# max21100_v3.net
KiCad netlist of a schematic drawn in EAGLE
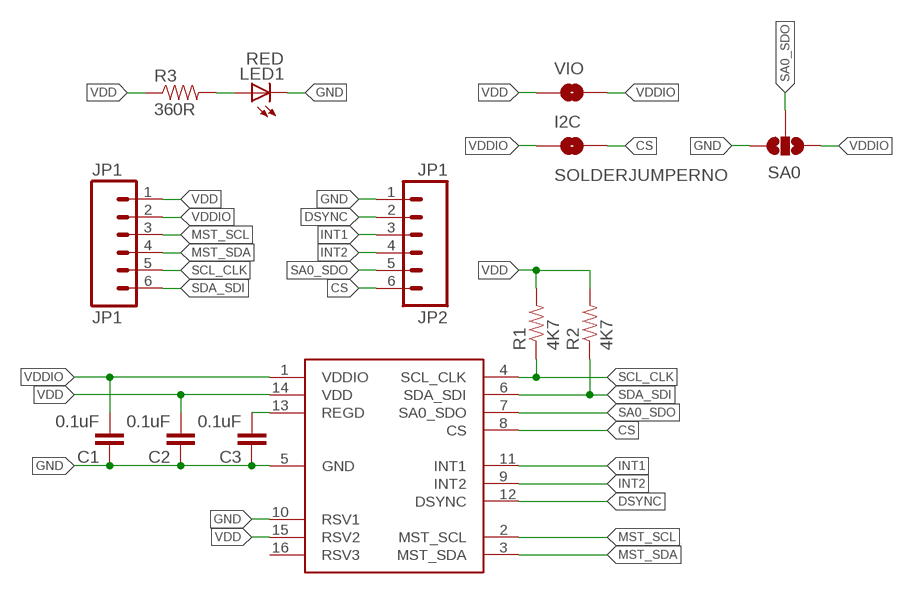
[diagram p0: schematic, sheet 1]

(export (version "E")
  (design (tool "Eeschema 10.0.6"))
  (components
    (comp (ref "C1")
      (value "0.1uF")
      (footprint "eagle-import:0603-CAP")
      (libsource (lib "eagle-import") (part "CAP0603-CAP"))
    )
    (comp (ref "C2")
      (value "0.1uF")
      (footprint "eagle-import:0603-CAP")
      (libsource (lib "eagle-import") (part "CAP0603-CAP"))
    )
    (comp (ref "C3")
      (value "0.1uF")
      (footprint "eagle-import:0603-CAP")
      (libsource (lib "eagle-import") (part "CAP0603-CAP"))
    )
    (comp (ref "I2C")
      (value "SOLDERJUMPERNO")
      (footprint "eagle-import:SJ_2S-NO")
      (libsource (lib "eagle-import") (part "SOLDERJUMPERNO"))
    )
    (comp (ref "JP1")
      (value "JP1")
      (footprint "eagle-import:1X06")
      (libsource (lib "eagle-import") (part "M06SIP"))
    )
    (comp (ref "JP2")
      (value "JP1")
      (footprint "eagle-import:1X06")
      (libsource (lib "eagle-import") (part "M06SIP"))
    )
    (comp (ref "LED1")
      (value "RED")
      (footprint "eagle-import:CHIP-LED0603")
      (libsource (lib "eagle-import") (part "LEDCHIP-LED0603"))
    )
    (comp (ref "R1")
      (value "4K7")
      (footprint "eagle-import:0603-RES")
      (libsource (lib "eagle-import") (part "RESISTOR0603-RES"))
    )
    (comp (ref "R2")
      (value "4K7")
      (footprint "eagle-import:0603-RES")
      (libsource (lib "eagle-import") (part "RESISTOR0603-RES"))
    )
    (comp (ref "R3")
      (value "360R")
      (footprint "eagle-import:0603-RES")
      (libsource (lib "eagle-import") (part "RESISTOR0603-RES"))
    )
    (comp (ref "SA0")
      (value "SOLDERJUMPER_2WAYS")
      (footprint "eagle-import:SJ_3")
      (libsource (lib "eagle-import") (part "SOLDERJUMPER_2WAYS"))
    )
    (comp (ref "U$1")
      (value "MAX21100")
      (footprint "eagle-import:MAX21100")
      (libsource (lib "eagle-import") (part "MAX21100"))
    )
    (comp (ref "VIO")
      (value "SOLDERJUMPERTRACE")
      (footprint "eagle-import:SJ_2S-TRACE")
      (libsource (lib "eagle-import") (part "SOLDERJUMPERTRACE"))
    )
  )
  (nets
    (net (code "1") (name "CS") (class "Default")
      (node (ref "I2C") (pin "2") (pinfunction "2_2") (pintype "passive"))
      (node (ref "JP2") (pin "6") (pinfunction "6_6") (pintype "passive"))
      (node (ref "U$1") (pin "8") (pinfunction "CS_8") (pintype "bidirectional"))
    )
    (net (code "2") (name "DSYNC") (class "Default")
      (node (ref "JP2") (pin "2") (pinfunction "2_2") (pintype "passive"))
      (node (ref "U$1") (pin "12") (pinfunction "DSYNC_12") (pintype "bidirectional"))
    )
    (net (code "3") (name "GND") (class "Default")
      (node (ref "C1") (pin "1") (pinfunction "1_1") (pintype "passive"))
      (node (ref "C2") (pin "1") (pinfunction "1_1") (pintype "passive"))
      (node (ref "C3") (pin "1") (pinfunction "1_1") (pintype "passive"))
      (node (ref "JP2") (pin "1") (pinfunction "1_1") (pintype "passive"))
      (node (ref "LED1") (pin "C") (pinfunction "C_C") (pintype "passive"))
      (node (ref "SA0") (pin "1") (pinfunction "1_1") (pintype "passive"))
      (node (ref "U$1") (pin "10") (pinfunction "RSV1_10") (pintype "bidirectional"))
      (node (ref "U$1") (pin "5") (pinfunction "GND_5") (pintype "bidirectional"))
    )
    (net (code "4") (name "INT1") (class "Default")
      (node (ref "JP2") (pin "3") (pinfunction "3_3") (pintype "passive"))
      (node (ref "U$1") (pin "11") (pinfunction "INT1_11") (pintype "bidirectional"))
    )
    (net (code "5") (name "INT2") (class "Default")
      (node (ref "JP2") (pin "4") (pinfunction "4_4") (pintype "passive"))
      (node (ref "U$1") (pin "9") (pinfunction "INT2_9") (pintype "bidirectional"))
    )
    (net (code "6") (name "MST_SCL") (class "Default")
      (node (ref "JP1") (pin "3") (pinfunction "3_3") (pintype "passive"))
      (node (ref "U$1") (pin "2") (pinfunction "MST_SCL_2") (pintype "bidirectional"))
    )
    (net (code "7") (name "MST_SDA") (class "Default")
      (node (ref "JP1") (pin "4") (pinfunction "4_4") (pintype "passive"))
      (node (ref "U$1") (pin "3") (pinfunction "MST_SDA_3") (pintype "bidirectional"))
    )
    (net (code "8") (name "Net-(LED1-PadA)") (class "Default")
      (node (ref "LED1") (pin "A") (pinfunction "A_A") (pintype "passive"))
      (node (ref "R3") (pin "2") (pinfunction "2_2") (pintype "passive"))
    )
    (net (code "9") (name "Net-(U$1-REGD)") (class "Default")
      (node (ref "C3") (pin "2") (pinfunction "2_2") (pintype "passive"))
      (node (ref "U$1") (pin "13") (pinfunction "REGD_13") (pintype "bidirectional"))
    )
    (net (code "10") (name "SA0_SDO") (class "Default")
      (node (ref "JP2") (pin "5") (pinfunction "5_5") (pintype "passive"))
      (node (ref "SA0") (pin "2") (pinfunction "2_2") (pintype "passive"))
      (node (ref "U$1") (pin "7") (pinfunction "SA0_SDO_7") (pintype "bidirectional"))
    )
    (net (code "11") (name "SCL_CLK") (class "Default")
      (node (ref "JP1") (pin "5") (pinfunction "5_5") (pintype "passive"))
      (node (ref "R1") (pin "1") (pinfunction "1_1") (pintype "passive"))
      (node (ref "U$1") (pin "4") (pinfunction "SCL_CLK_4") (pintype "bidirectional"))
    )
    (net (code "12") (name "SDA_SDI") (class "Default")
      (node (ref "JP1") (pin "6") (pinfunction "6_6") (pintype "passive"))
      (node (ref "R2") (pin "1") (pinfunction "1_1") (pintype "passive"))
      (node (ref "U$1") (pin "6") (pinfunction "SDA_SDI_6") (pintype "bidirectional"))
    )
    (net (code "13") (name "VDD") (class "Default")
      (node (ref "C2") (pin "2") (pinfunction "2_2") (pintype "passive"))
      (node (ref "JP1") (pin "1") (pinfunction "1_1") (pintype "passive"))
      (node (ref "R1") (pin "2") (pinfunction "2_2") (pintype "passive"))
      (node (ref "R2") (pin "2") (pinfunction "2_2") (pintype "passive"))
      (node (ref "R3") (pin "1") (pinfunction "1_1") (pintype "passive"))
      (node (ref "U$1") (pin "14") (pinfunction "VDD_14") (pintype "bidirectional"))
      (node (ref "U$1") (pin "15") (pinfunction "RSV2_15") (pintype "bidirectional"))
      (node (ref "VIO") (pin "1") (pinfunction "1_1") (pintype "passive"))
    )
    (net (code "14") (name "VDDIO") (class "Default")
      (node (ref "C1") (pin "2") (pinfunction "2_2") (pintype "passive"))
      (node (ref "I2C") (pin "1") (pinfunction "1_1") (pintype "passive"))
      (node (ref "JP1") (pin "2") (pinfunction "2_2") (pintype "passive"))
      (node (ref "SA0") (pin "3") (pinfunction "3_3") (pintype "passive"))
      (node (ref "U$1") (pin "1") (pinfunction "VDDIO_1") (pintype "bidirectional"))
      (node (ref "VIO") (pin "2") (pinfunction "2_2") (pintype "passive"))
    )
    (net (code "15") (name "unconnected-(U$1-RSV3-Pad16)") (class "Default")
      (node (ref "U$1") (pin "16") (pinfunction "RSV3_16") (pintype "bidirectional"))
    )
  )
)
